# LEDDriver_v_4.net
KiCad netlist of a schematic drawn in EAGLE
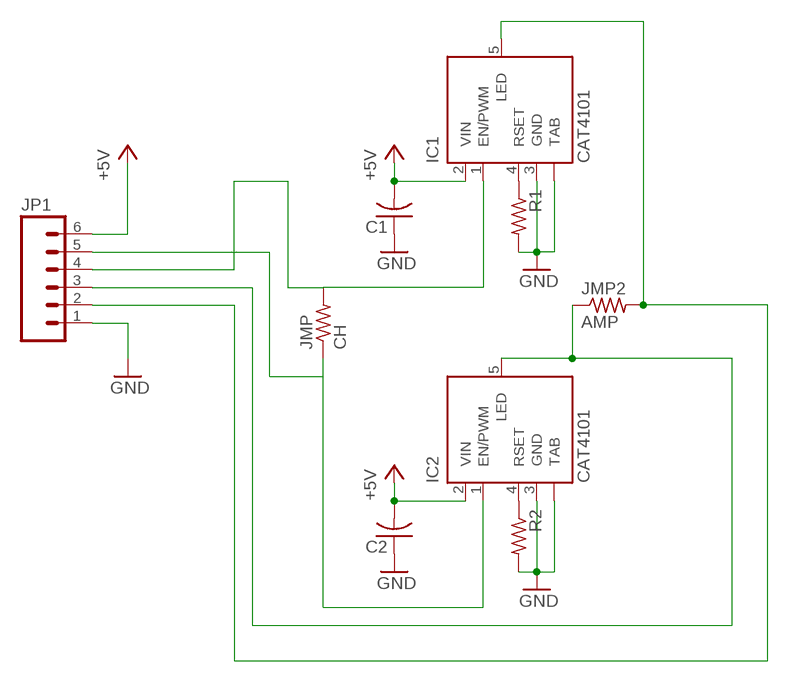
[diagram p0: schematic, sheet 1]

(export (version "E")
  (design (tool "Eeschema 10.0.6"))
  (components
    (comp (ref "C1")
      (value "C-USC1206")
      (footprint "eagle-import:C1206")
      (libsource (lib "eagle-import") (part "C-USC1206"))
    )
    (comp (ref "C2")
      (value "C-USC1206")
      (footprint "eagle-import:C1206")
      (libsource (lib "eagle-import") (part "C-USC1206"))
    )
    (comp (ref "IC1")
      (value "CAT4101")
      (footprint "eagle-import:TO263_5")
      (fields (field (name "MPN") "CAT4101TV-T75"))
      (libsource (lib "eagle-import") (part "CAT4101"))
    )
    (comp (ref "IC2")
      (value "CAT4101")
      (footprint "eagle-import:TO263_5")
      (fields (field (name "MPN") "CAT4101TV-T75"))
      (libsource (lib "eagle-import") (part "CAT4101"))
    )
    (comp (ref "JMP")
      (value "CH")
      (footprint "eagle-import:R1206")
      (libsource (lib "eagle-import") (part "R-US_R1206"))
    )
    (comp (ref "JMP2")
      (value "AMP")
      (footprint "eagle-import:R1206")
      (libsource (lib "eagle-import") (part "R-US_R1206"))
    )
    (comp (ref "JP1")
      (value "M06POGOPIN_HOLES_ONLY")
      (footprint "eagle-import:1X06_HOLES_ONLY")
      (libsource (lib "eagle-import") (part "M06POGOPIN_HOLES_ONLY"))
    )
    (comp (ref "R1")
      (value "R-US_R1206")
      (footprint "eagle-import:R1206")
      (libsource (lib "eagle-import") (part "R-US_R1206"))
    )
    (comp (ref "R2")
      (value "R-US_R1206")
      (footprint "eagle-import:R1206")
      (libsource (lib "eagle-import") (part "R-US_R1206"))
    )
  )
  (nets
    (net (code "1") (name "+5V") (class "Default")
      (node (ref "C1") (pin "2") (pinfunction "2_2") (pintype "passive"))
      (node (ref "C2") (pin "2") (pinfunction "2_2") (pintype "passive"))
      (node (ref "IC1") (pin "2") (pinfunction "VIN_2") (pintype "input"))
      (node (ref "IC2") (pin "2") (pinfunction "VIN_2") (pintype "input"))
      (node (ref "JP1") (pin "6") (pinfunction "6_6") (pintype "passive"))
    )
    (net (code "2") (name "GND") (class "Default")
      (node (ref "C1") (pin "1") (pinfunction "1_1") (pintype "passive"))
      (node (ref "C2") (pin "1") (pinfunction "1_1") (pintype "passive"))
      (node (ref "IC1") (pin "3") (pinfunction "GND_3") (pintype "power_in"))
      (node (ref "IC1") (pin "TAB") (pinfunction "TAB_TAB") (pintype "passive"))
      (node (ref "IC2") (pin "3") (pinfunction "GND_3") (pintype "power_in"))
      (node (ref "IC2") (pin "TAB") (pinfunction "TAB_TAB") (pintype "passive"))
      (node (ref "JP1") (pin "1") (pinfunction "1_1") (pintype "passive"))
      (node (ref "R1") (pin "2") (pinfunction "2_2") (pintype "passive"))
      (node (ref "R2") (pin "2") (pinfunction "2_2") (pintype "passive"))
    )
    (net (code "3") (name "Net-(IC1-EN{slash}PWM)") (class "Default")
      (node (ref "IC1") (pin "1") (pinfunction "EN/PWM_1") (pintype "input"))
      (node (ref "JMP") (pin "2") (pinfunction "2_2") (pintype "passive"))
      (node (ref "JP1") (pin "4") (pinfunction "4_4") (pintype "passive"))
    )
    (net (code "4") (name "Net-(IC1-LED)") (class "Default")
      (node (ref "IC1") (pin "5") (pinfunction "LED_5") (pintype "power_in"))
      (node (ref "JMP2") (pin "2") (pinfunction "2_2") (pintype "passive"))
      (node (ref "JP1") (pin "2") (pinfunction "2_2") (pintype "passive"))
    )
    (net (code "5") (name "Net-(IC1-RSET)") (class "Default")
      (node (ref "IC1") (pin "4") (pinfunction "RSET_4") (pintype "input"))
      (node (ref "R1") (pin "1") (pinfunction "1_1") (pintype "passive"))
    )
    (net (code "6") (name "Net-(IC2-EN{slash}PWM)") (class "Default")
      (node (ref "IC2") (pin "1") (pinfunction "EN/PWM_1") (pintype "input"))
      (node (ref "JMP") (pin "1") (pinfunction "1_1") (pintype "passive"))
      (node (ref "JP1") (pin "5") (pinfunction "5_5") (pintype "passive"))
    )
    (net (code "7") (name "Net-(IC2-LED)") (class "Default")
      (node (ref "IC2") (pin "5") (pinfunction "LED_5") (pintype "power_in"))
      (node (ref "JMP2") (pin "1") (pinfunction "1_1") (pintype "passive"))
      (node (ref "JP1") (pin "3") (pinfunction "3_3") (pintype "passive"))
    )
    (net (code "8") (name "Net-(IC2-RSET)") (class "Default")
      (node (ref "IC2") (pin "4") (pinfunction "RSET_4") (pintype "input"))
      (node (ref "R2") (pin "1") (pinfunction "1_1") (pintype "passive"))
    )
  )
)
